# MCU.net
KiCad netlist of a schematic drawn in EAGLE
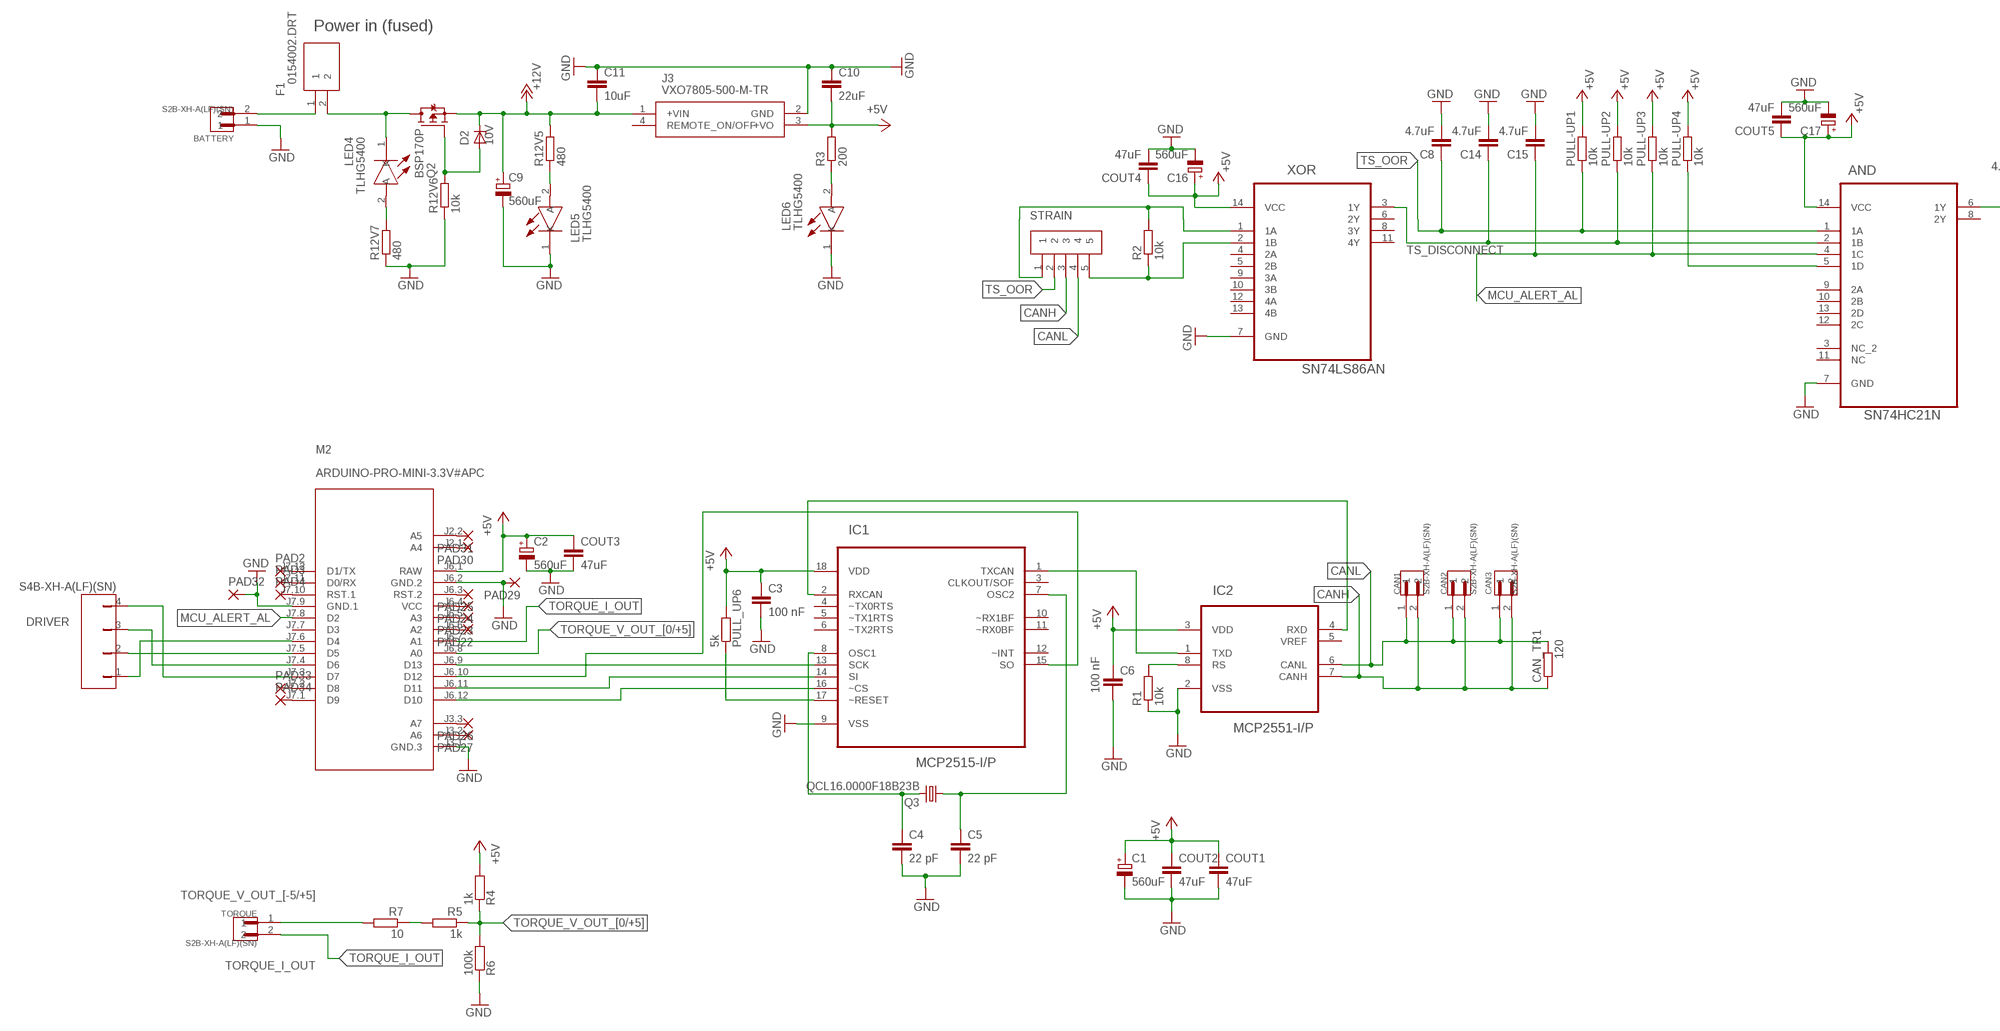
[diagram p0: schematic, sheet 1, part 1 of 2]
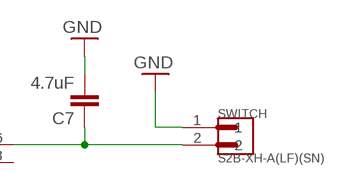
[diagram p1: schematic, sheet 1, part 2 of 2]

(export (version "E")
  (design (tool "Eeschema 10.0.6"))
  (components
    (comp (ref "AND")
      (value "SN74HC21N")
      (footprint "eagle-import:DIP254P762X508-14")
      (fields (field (name "MF") "Texas Instruments"))
      (libsource (lib "eagle-import") (part "SN74HC21N"))
    )
    (comp (ref "BATTERY")
      (value "S2B-XH-A(LF)(SN)")
      (footprint "eagle-import:JST_S2B-XH-A(LF)(SN)")
      (fields
        (field (name "DIGI-KEY_PART_NUMBER") "455-2257-ND")
        (field (name "MF") "JST Sales")
        (field (name "MP") "S2B-XH-A_LF__SN_")
      )
      (libsource (lib "eagle-import") (part "S2B-XH-A(LF)(SN)"))
    )
    (comp (ref "C1")
      (value "560uF")
      (footprint "eagle-import:PANASONIC_F")
      (libsource (lib "eagle-import") (part "CPOL-EUF"))
    )
    (comp (ref "C2")
      (value "560uF")
      (footprint "eagle-import:PANASONIC_F")
      (libsource (lib "eagle-import") (part "CPOL-EUF"))
    )
    (comp (ref "C3")
      (value "100 nF")
      (footprint "eagle-import:C0805")
      (libsource (lib "eagle-import") (part "C-EUC0805"))
    )
    (comp (ref "C4")
      (value "22 pF")
      (footprint "eagle-import:C0805")
      (libsource (lib "eagle-import") (part "C-EUC0805"))
    )
    (comp (ref "C5")
      (value "22 pF")
      (footprint "eagle-import:C0805")
      (libsource (lib "eagle-import") (part "C-EUC0805"))
    )
    (comp (ref "C6")
      (value "100 nF")
      (footprint "eagle-import:C0805")
      (libsource (lib "eagle-import") (part "C-EUC0805"))
    )
    (comp (ref "C7")
      (value "4.7uF")
      (footprint "eagle-import:C0805")
      (libsource (lib "eagle-import") (part "C-EUC0805"))
    )
    (comp (ref "C8")
      (value "4.7uF")
      (footprint "eagle-import:C0805")
      (libsource (lib "eagle-import") (part "C-EUC0805"))
    )
    (comp (ref "C9")
      (value "560uF")
      (footprint "eagle-import:PANASONIC_F")
      (libsource (lib "eagle-import") (part "CPOL-EUF"))
    )
    (comp (ref "C10")
      (value "22uF")
      (footprint "eagle-import:C0805")
      (libsource (lib "eagle-import") (part "C-EUC0805"))
    )
    (comp (ref "C11")
      (value "10uF")
      (footprint "eagle-import:C0805")
      (libsource (lib "eagle-import") (part "C-EUC0805"))
    )
    (comp (ref "C14")
      (value "4.7uF")
      (footprint "eagle-import:C0805")
      (libsource (lib "eagle-import") (part "C-EUC0805"))
    )
    (comp (ref "C15")
      (value "4.7uF")
      (footprint "eagle-import:C0805")
      (libsource (lib "eagle-import") (part "C-EUC0805"))
    )
    (comp (ref "C16")
      (value "560uF")
      (footprint "eagle-import:PANASONIC_F")
      (libsource (lib "eagle-import") (part "CPOL-EUF"))
    )
    (comp (ref "C17")
      (value "560uF")
      (footprint "eagle-import:PANASONIC_F")
      (libsource (lib "eagle-import") (part "CPOL-EUF"))
    )
    (comp (ref "CAN1")
      (value "S2B-XH-A(LF)(SN)")
      (footprint "eagle-import:JST_S2B-XH-A(LF)(SN)")
      (fields
        (field (name "DIGI-KEY_PART_NUMBER") "455-2257-ND")
        (field (name "MF") "JST Sales")
        (field (name "MP") "S2B-XH-A_LF__SN_")
      )
      (libsource (lib "eagle-import") (part "S2B-XH-A(LF)(SN)"))
    )
    (comp (ref "CAN2")
      (value "S2B-XH-A(LF)(SN)")
      (footprint "eagle-import:JST_S2B-XH-A(LF)(SN)")
      (fields
        (field (name "DIGI-KEY_PART_NUMBER") "455-2257-ND")
        (field (name "MF") "JST Sales")
        (field (name "MP") "S2B-XH-A_LF__SN_")
      )
      (libsource (lib "eagle-import") (part "S2B-XH-A(LF)(SN)"))
    )
    (comp (ref "CAN3")
      (value "S2B-XH-A(LF)(SN)")
      (footprint "eagle-import:JST_S2B-XH-A(LF)(SN)")
      (fields
        (field (name "DIGI-KEY_PART_NUMBER") "455-2257-ND")
        (field (name "MF") "JST Sales")
        (field (name "MP") "S2B-XH-A_LF__SN_")
      )
      (libsource (lib "eagle-import") (part "S2B-XH-A(LF)(SN)"))
    )
    (comp (ref "CAN_TR1")
      (value "120")
      (footprint "eagle-import:R0805")
      (libsource (lib "eagle-import") (part "R-EU_R0805"))
    )
    (comp (ref "COUT1")
      (value "47uF")
      (footprint "eagle-import:C0805")
      (libsource (lib "eagle-import") (part "C-EUC0805"))
    )
    (comp (ref "COUT2")
      (value "47uF")
      (footprint "eagle-import:C0805")
      (libsource (lib "eagle-import") (part "C-EUC0805"))
    )
    (comp (ref "COUT3")
      (value "47uF")
      (footprint "eagle-import:C0805")
      (libsource (lib "eagle-import") (part "C-EUC0805"))
    )
    (comp (ref "COUT4")
      (value "47uF")
      (footprint "eagle-import:C0805")
      (libsource (lib "eagle-import") (part "C-EUC0805"))
    )
    (comp (ref "COUT5")
      (value "47uF")
      (footprint "eagle-import:C0805")
      (libsource (lib "eagle-import") (part "C-EUC0805"))
    )
    (comp (ref "D2")
      (value "10V")
      (footprint "eagle-import:SMB")
      (libsource (lib "eagle-import") (part "ZENER-DIODESMB"))
    )
    (comp (ref "DRIVER")
      (value "S4B-XH-A(LF)(SN)")
      (footprint "eagle-import:S4B-XH-A(LF)(SN)")
      (fields (field (name "MF") "JST Sales") (field (name "MP") "S4B-XH-A_LF__SN_"))
      (libsource (lib "eagle-import") (part "S4B-XH-A(LF)(SN)"))
    )
    (comp (ref "F1")
      (value "0154002.DRT")
      (footprint "eagle-import:FUSM9750X381N")
      (fields (field (name "MOUSER_PART_NUMBER") "576-0154002.DRT"))
      (libsource (lib "eagle-import") (part "0154002.DRT"))
    )
    (comp (ref "IC1")
      (value "MCP2515-I/P")
      (footprint "eagle-import:DIP254P762X432-18")
      (fields (field (name "MF") "Microchip"))
      (libsource (lib "eagle-import") (part "MCP2515-I/P"))
    )
    (comp (ref "IC2")
      (value "MCP2551-I/P")
      (footprint "eagle-import:DIP254P762X432-8")
      (fields (field (name "MF") "Microchip"))
      (libsource (lib "eagle-import") (part "MCP2551-I/P"))
    )
    (comp (ref "J3")
      (value "VXO7805-500-M-TR")
      (footprint "eagle-import:VXO7805500MTR")
      (fields (field (name "MOUSER_PART_NUMBER") "490-VXO7805-500-M-TR"))
      (libsource (lib "eagle-import") (part "VXO7805-500-M-TR"))
    )
    (comp (ref "LED4")
      (value "TLHG5400")
      (footprint "eagle-import:TLHG5400")
      (fields (field (name "MOUSER_PART_NUMBER") "78-TLHG5400"))
      (libsource (lib "eagle-import") (part "TLHG5400"))
    )
    (comp (ref "LED5")
      (value "TLHG5400")
      (footprint "eagle-import:TLHG5400")
      (fields (field (name "MOUSER_PART_NUMBER") "78-TLHG5400"))
      (libsource (lib "eagle-import") (part "TLHG5400"))
    )
    (comp (ref "LED6")
      (value "TLHG5400")
      (footprint "eagle-import:TLHG5400")
      (fields (field (name "MOUSER_PART_NUMBER") "78-TLHG5400"))
      (libsource (lib "eagle-import") (part "TLHG5400"))
    )
    (comp (ref "M2")
      (value "ARDUINO-PRO-MINI-3.3V#APC")
      (footprint "eagle-import:ARDUINO-PRO-MINI#APC")
      (libsource (lib "eagle-import") (part "ARDUINO-PRO-MINI-#APC3.3V"))
    )
    (comp (ref "PAD2")
      (value "SMD2")
      (footprint "eagle-import:SMD1,27-2,54")
      (libsource (lib "eagle-import") (part "SMD2"))
    )
    (comp (ref "PAD3")
      (value "SMD2")
      (footprint "eagle-import:SMD1,27-2,54")
      (libsource (lib "eagle-import") (part "SMD2"))
    )
    (comp (ref "PAD4")
      (value "SMD2")
      (footprint "eagle-import:SMD1,27-2,54")
      (libsource (lib "eagle-import") (part "SMD2"))
    )
    (comp (ref "PAD22")
      (value "SMD2")
      (footprint "eagle-import:SMD1,27-2,54")
      (libsource (lib "eagle-import") (part "SMD2"))
    )
    (comp (ref "PAD23")
      (value "SMD2")
      (footprint "eagle-import:SMD1,27-2,54")
      (libsource (lib "eagle-import") (part "SMD2"))
    )
    (comp (ref "PAD24")
      (value "SMD2")
      (footprint "eagle-import:SMD1,27-2,54")
      (libsource (lib "eagle-import") (part "SMD2"))
    )
    (comp (ref "PAD25")
      (value "SMD2")
      (footprint "eagle-import:SMD1,27-2,54")
      (libsource (lib "eagle-import") (part "SMD2"))
    )
    (comp (ref "PAD26")
      (value "SMD2")
      (footprint "eagle-import:SMD1,27-2,54")
      (libsource (lib "eagle-import") (part "SMD2"))
    )
    (comp (ref "PAD27")
      (value "SMD2")
      (footprint "eagle-import:SMD1,27-2,54")
      (libsource (lib "eagle-import") (part "SMD2"))
    )
    (comp (ref "PAD29")
      (value "SMD2")
      (footprint "eagle-import:SMD1,27-2,54")
      (libsource (lib "eagle-import") (part "SMD2"))
    )
    (comp (ref "PAD30")
      (value "SMD2")
      (footprint "eagle-import:SMD1,27-2,54")
      (libsource (lib "eagle-import") (part "SMD2"))
    )
    (comp (ref "PAD31")
      (value "SMD2")
      (footprint "eagle-import:SMD1,27-2,54")
      (libsource (lib "eagle-import") (part "SMD2"))
    )
    (comp (ref "PAD32")
      (value "SMD2")
      (footprint "eagle-import:SMD1,27-2,54")
      (libsource (lib "eagle-import") (part "SMD2"))
    )
    (comp (ref "PAD33")
      (value "SMD2")
      (footprint "eagle-import:SMD1,27-2,54")
      (libsource (lib "eagle-import") (part "SMD2"))
    )
    (comp (ref "PAD34")
      (value "SMD2")
      (footprint "eagle-import:SMD1,27-2,54")
      (libsource (lib "eagle-import") (part "SMD2"))
    )
    (comp (ref "PULL-UP1")
      (value "10k")
      (footprint "eagle-import:R0805")
      (libsource (lib "eagle-import") (part "R-EU_R0805"))
    )
    (comp (ref "PULL-UP2")
      (value "10k")
      (footprint "eagle-import:R0805")
      (libsource (lib "eagle-import") (part "R-EU_R0805"))
    )
    (comp (ref "PULL-UP3")
      (value "10k")
      (footprint "eagle-import:R0805")
      (libsource (lib "eagle-import") (part "R-EU_R0805"))
    )
    (comp (ref "PULL-UP4")
      (value "10k")
      (footprint "eagle-import:R0805")
      (libsource (lib "eagle-import") (part "R-EU_R0805"))
    )
    (comp (ref "PULL_UP6")
      (value "5k")
      (footprint "eagle-import:R0805")
      (libsource (lib "eagle-import") (part "R-EU_R0805"))
    )
    (comp (ref "Q2")
      (value "BSP170P")
      (footprint "eagle-import:SOT223")
      (libsource (lib "eagle-import") (part "BSP170P"))
    )
    (comp (ref "Q3")
      (value "QCL16.0000F18B23B")
      (footprint "eagle-import:HC49_S")
      (libsource (lib "eagle-import") (part "CRYSTALHC49S"))
    )
    (comp (ref "R1")
      (value "10k")
      (footprint "eagle-import:R0805")
      (libsource (lib "eagle-import") (part "R-EU_R0805"))
    )
    (comp (ref "R2")
      (value "10k")
      (footprint "eagle-import:R0805")
      (libsource (lib "eagle-import") (part "R-EU_R0805"))
    )
    (comp (ref "R3")
      (value "200")
      (footprint "eagle-import:R0805")
      (libsource (lib "eagle-import") (part "R-EU_R0805"))
    )
    (comp (ref "R4")
      (value "1k")
      (footprint "eagle-import:R0805")
      (libsource (lib "eagle-import") (part "R-EU_R0805"))
    )
    (comp (ref "R5")
      (value "1k")
      (footprint "eagle-import:R0805")
      (libsource (lib "eagle-import") (part "R-EU_R0805"))
    )
    (comp (ref "R6")
      (value "100k")
      (footprint "eagle-import:R0805")
      (libsource (lib "eagle-import") (part "R-EU_R0805"))
    )
    (comp (ref "R7")
      (value "10")
      (footprint "eagle-import:R0805")
      (libsource (lib "eagle-import") (part "R-EU_R0805"))
    )
    (comp (ref "R12V5")
      (value "480")
      (footprint "eagle-import:R0805")
      (libsource (lib "eagle-import") (part "R-EU_R0805"))
    )
    (comp (ref "R12V6")
      (value "10k")
      (footprint "eagle-import:R0805")
      (libsource (lib "eagle-import") (part "R-EU_R0805"))
    )
    (comp (ref "R12V7")
      (value "480")
      (footprint "eagle-import:R0805")
      (libsource (lib "eagle-import") (part "R-EU_R0805"))
    )
    (comp (ref "STRAIN")
      (value "S5B-XH-A(LF)(SN)")
      (footprint "eagle-import:JST_S5B-XH-A(LF)(SN)")
      (fields (field (name "MF") "JST Sales") (field (name "MP") "S5B-XH-A_LF__SN_"))
      (libsource (lib "eagle-import") (part "S5B-XH-A(LF)(SN)"))
    )
    (comp (ref "SWITCH")
      (value "S2B-XH-A(LF)(SN)")
      (footprint "eagle-import:JST_S2B-XH-A(LF)(SN)")
      (fields
        (field (name "DIGI-KEY_PART_NUMBER") "455-2257-ND")
        (field (name "MF") "JST Sales")
        (field (name "MP") "S2B-XH-A_LF__SN_")
      )
      (libsource (lib "eagle-import") (part "S2B-XH-A(LF)(SN)"))
    )
    (comp (ref "TORQUE")
      (value "S2B-XH-A(LF)(SN)")
      (footprint "eagle-import:JST_S2B-XH-A(LF)(SN)")
      (fields
        (field (name "DIGI-KEY_PART_NUMBER") "455-2257-ND")
        (field (name "MF") "JST Sales")
        (field (name "MP") "S2B-XH-A_LF__SN_")
      )
      (libsource (lib "eagle-import") (part "S2B-XH-A(LF)(SN)"))
    )
    (comp (ref "XOR")
      (value "SN74LS86AN")
      (footprint "eagle-import:DIP254P762X508-14")
      (fields (field (name "MF") "Texas Instruments"))
      (libsource (lib "eagle-import") (part "SN74LS86AN"))
    )
  )
  (nets
    (net (code "1") (name "+5V") (class "Default")
      (node (ref "AND") (pin "14") (pinfunction "VCC_14") (pintype "power_in"))
      (node (ref "C1") (pin "+") (pinfunction "+_+") (pintype "passive"))
      (node (ref "C10") (pin "2") (pinfunction "2_2") (pintype "passive"))
      (node (ref "C16") (pin "+") (pinfunction "+_+") (pintype "passive"))
      (node (ref "C17") (pin "+") (pinfunction "+_+") (pintype "passive"))
      (node (ref "C2") (pin "+") (pinfunction "+_+") (pintype "passive"))
      (node (ref "C3") (pin "1") (pinfunction "1_1") (pintype "passive"))
      (node (ref "C6") (pin "1") (pinfunction "1_1") (pintype "passive"))
      (node (ref "COUT1") (pin "1") (pinfunction "1_1") (pintype "passive"))
      (node (ref "COUT2") (pin "1") (pinfunction "1_1") (pintype "passive"))
      (node (ref "COUT3") (pin "1") (pinfunction "1_1") (pintype "passive"))
      (node (ref "COUT4") (pin "1") (pinfunction "1_1") (pintype "passive"))
      (node (ref "COUT5") (pin "1") (pinfunction "1_1") (pintype "passive"))
      (node (ref "IC1") (pin "18") (pinfunction "VDD_18") (pintype "power_in"))
      (node (ref "IC2") (pin "3") (pinfunction "VDD_3") (pintype "power_in"))
      (node (ref "J3") (pin "3") (pinfunction "+VO_3") (pintype "bidirectional"))
      (node (ref "M2") (pin "J6.1") (pinfunction "RAW_J6.1") (pintype "power_in"))
      (node (ref "PULL-UP1") (pin "2") (pinfunction "2_2") (pintype "passive"))
      (node (ref "PULL-UP2") (pin "2") (pinfunction "2_2") (pintype "passive"))
      (node (ref "PULL-UP3") (pin "2") (pinfunction "2_2") (pintype "passive"))
      (node (ref "PULL-UP4") (pin "2") (pinfunction "2_2") (pintype "passive"))
      (node (ref "PULL_UP6") (pin "2") (pinfunction "2_2") (pintype "passive"))
      (node (ref "R3") (pin "2") (pinfunction "2_2") (pintype "passive"))
      (node (ref "R4") (pin "2") (pinfunction "2_2") (pintype "passive"))
      (node (ref "XOR") (pin "14") (pinfunction "VCC_14") (pintype "power_in"))
    )
    (net (code "2") (name "+12V") (class "Default")
      (node (ref "C11") (pin "2") (pinfunction "2_2") (pintype "passive"))
      (node (ref "C9") (pin "+") (pinfunction "+_+") (pintype "passive"))
      (node (ref "D2") (pin "C") (pinfunction "C_C") (pintype "passive"))
      (node (ref "J3") (pin "1") (pinfunction "+VIN_1") (pintype "bidirectional"))
      (node (ref "Q2") (pin "3") (pinfunction "S_3") (pintype "passive"))
      (node (ref "R12V5") (pin "2") (pinfunction "2_2") (pintype "passive"))
    )
    (net (code "3") (name "/TORQUE_V_OUT_[-5{slash}+5]") (class "Default")
      (node (ref "R7") (pin "2") (pinfunction "2_2") (pintype "passive"))
      (node (ref "TORQUE") (pin "1") (pinfunction "1_1") (pintype "passive"))
    )
    (net (code "4") (name "/TS_DISCONNECT") (class "Default")
      (node (ref "AND") (pin "2") (pinfunction "1B_2") (pintype "input"))
      (node (ref "C14") (pin "1") (pinfunction "1_1") (pintype "passive"))
      (node (ref "PULL-UP2") (pin "1") (pinfunction "1_1") (pintype "passive"))
      (node (ref "XOR") (pin "3") (pinfunction "1Y_3") (pintype "output"))
    )
    (net (code "5") (name "CANH") (class "Default")
      (node (ref "CAN1") (pin "2") (pinfunction "2_2") (pintype "passive"))
      (node (ref "CAN2") (pin "2") (pinfunction "2_2") (pintype "passive"))
      (node (ref "CAN3") (pin "2") (pinfunction "2_2") (pintype "passive"))
      (node (ref "CAN_TR1") (pin "1") (pinfunction "1_1") (pintype "passive"))
      (node (ref "IC2") (pin "7") (pinfunction "CANH_7") (pintype "bidirectional"))
      (node (ref "STRAIN") (pin "3") (pinfunction "3_3") (pintype "passive"))
    )
    (net (code "6") (name "CANL") (class "Default")
      (node (ref "CAN1") (pin "1") (pinfunction "1_1") (pintype "passive"))
      (node (ref "CAN2") (pin "1") (pinfunction "1_1") (pintype "passive"))
      (node (ref "CAN3") (pin "1") (pinfunction "1_1") (pintype "passive"))
      (node (ref "CAN_TR1") (pin "2") (pinfunction "2_2") (pintype "passive"))
      (node (ref "IC2") (pin "6") (pinfunction "CANL_6") (pintype "bidirectional"))
      (node (ref "STRAIN") (pin "4") (pinfunction "4_4") (pintype "passive"))
    )
    (net (code "7") (name "GND") (class "Default")
      (node (ref "AND") (pin "7") (pinfunction "GND_7") (pintype "passive"))
      (node (ref "BATTERY") (pin "1") (pinfunction "1_1") (pintype "passive"))
      (node (ref "C1") (pin "-") (pinfunction "-_-") (pintype "passive"))
      (node (ref "C10") (pin "1") (pinfunction "1_1") (pintype "passive"))
      (node (ref "C11") (pin "1") (pinfunction "1_1") (pintype "passive"))
      (node (ref "C14") (pin "2") (pinfunction "2_2") (pintype "passive"))
      (node (ref "C15") (pin "2") (pinfunction "2_2") (pintype "passive"))
      (node (ref "C16") (pin "-") (pinfunction "-_-") (pintype "passive"))
      (node (ref "C17") (pin "-") (pinfunction "-_-") (pintype "passive"))
      (node (ref "C2") (pin "-") (pinfunction "-_-") (pintype "passive"))
      (node (ref "C3") (pin "2") (pinfunction "2_2") (pintype "passive"))
      (node (ref "C4") (pin "2") (pinfunction "2_2") (pintype "passive"))
      (node (ref "C5") (pin "2") (pinfunction "2_2") (pintype "passive"))
      (node (ref "C6") (pin "2") (pinfunction "2_2") (pintype "passive"))
      (node (ref "C7") (pin "2") (pinfunction "2_2") (pintype "passive"))
      (node (ref "C8") (pin "2") (pinfunction "2_2") (pintype "passive"))
      (node (ref "C9") (pin "-") (pinfunction "-_-") (pintype "passive"))
      (node (ref "COUT1") (pin "2") (pinfunction "2_2") (pintype "passive"))
      (node (ref "COUT2") (pin "2") (pinfunction "2_2") (pintype "passive"))
      (node (ref "COUT3") (pin "2") (pinfunction "2_2") (pintype "passive"))
      (node (ref "COUT4") (pin "2") (pinfunction "2_2") (pintype "passive"))
      (node (ref "COUT5") (pin "2") (pinfunction "2_2") (pintype "passive"))
      (node (ref "IC1") (pin "9") (pinfunction "VSS_9") (pintype "power_in"))
      (node (ref "IC2") (pin "2") (pinfunction "VSS_2") (pintype "power_in"))
      (node (ref "J3") (pin "2") (pinfunction "GND_2") (pintype "bidirectional"))
      (node (ref "LED5") (pin "1") (pinfunction "K_1") (pintype "bidirectional"))
      (node (ref "LED6") (pin "1") (pinfunction "K_1") (pintype "bidirectional"))
      (node (ref "M2") (pin "J3.1") (pinfunction "GND.3_J3.1") (pintype "bidirectional"))
      (node (ref "M2") (pin "J6.2") (pinfunction "GND.2_J6.2") (pintype "power_in"))
      (node (ref "M2") (pin "J7.9") (pinfunction "GND.1_J7.9") (pintype "power_in"))
      (node (ref "PAD29") (pin "1") (pinfunction "P_1") (pintype "passive"))
      (node (ref "PAD32") (pin "1") (pinfunction "P_1") (pintype "passive"))
      (node (ref "R1") (pin "1") (pinfunction "1_1") (pintype "passive"))
      (node (ref "R12V6") (pin "1") (pinfunction "1_1") (pintype "passive"))
      (node (ref "R12V7") (pin "1") (pinfunction "1_1") (pintype "passive"))
      (node (ref "R6") (pin "1") (pinfunction "1_1") (pintype "passive"))
      (node (ref "SWITCH") (pin "1") (pinfunction "1_1") (pintype "passive"))
      (node (ref "XOR") (pin "7") (pinfunction "GND_7") (pintype "passive"))
    )
    (net (code "8") (name "MCU_ALERT_AL") (class "Default")
      (node (ref "AND") (pin "4") (pinfunction "1C_4") (pintype "input"))
      (node (ref "C15") (pin "1") (pinfunction "1_1") (pintype "passive"))
      (node (ref "M2") (pin "J7.8") (pinfunction "D2_J7.8") (pintype "bidirectional"))
      (node (ref "PULL-UP3") (pin "1") (pinfunction "1_1") (pintype "passive"))
    )
    (net (code "9") (name "Net-(AND-1D)") (class "Default")
      (node (ref "AND") (pin "5") (pinfunction "1D_5") (pintype "input"))
      (node (ref "PULL-UP4") (pin "1") (pinfunction "1_1") (pintype "passive"))
    )
    (net (code "10") (name "Net-(AND-1Y)") (class "Default")
      (node (ref "AND") (pin "6") (pinfunction "1Y_6") (pintype "output"))
      (node (ref "C7") (pin "1") (pinfunction "1_1") (pintype "passive"))
      (node (ref "SWITCH") (pin "2") (pinfunction "2_2") (pintype "passive"))
    )
    (net (code "11") (name "Net-(BATTERY-Pad2)") (class "Default")
      (node (ref "BATTERY") (pin "2") (pinfunction "2_2") (pintype "passive"))
      (node (ref "F1") (pin "1") (pinfunction "1_1") (pintype "bidirectional"))
    )
    (net (code "12") (name "Net-(IC1-OSC1)") (class "Default")
      (node (ref "C4") (pin "1") (pinfunction "1_1") (pintype "passive"))
      (node (ref "IC1") (pin "8") (pinfunction "OSC1_8") (pintype "input"))
      (node (ref "Q3") (pin "2") (pinfunction "2_2") (pintype "passive"))
    )
    (net (code "13") (name "Net-(IC1-OSC2)") (class "Default")
      (node (ref "C5") (pin "1") (pinfunction "1_1") (pintype "passive"))
      (node (ref "IC1") (pin "7") (pinfunction "OSC2_7") (pintype "output"))
      (node (ref "Q3") (pin "1") (pinfunction "1_1") (pintype "passive"))
    )
    (net (code "14") (name "Net-(IC1-RXCAN)") (class "Default")
      (node (ref "IC1") (pin "2") (pinfunction "RXCAN_2") (pintype "input"))
      (node (ref "IC2") (pin "4") (pinfunction "RXD_4") (pintype "output"))
    )
    (net (code "15") (name "Net-(IC1-SCK)") (class "Default")
      (node (ref "IC1") (pin "13") (pinfunction "SCK_13") (pintype "input"))
      (node (ref "M2") (pin "J6.9") (pinfunction "D13_J6.9") (pintype "bidirectional"))
    )
    (net (code "16") (name "Net-(IC1-SI)") (class "Default")
      (node (ref "IC1") (pin "14") (pinfunction "SI_14") (pintype "input"))
      (node (ref "M2") (pin "J6.11") (pinfunction "D11_J6.11") (pintype "bidirectional"))
    )
    (net (code "17") (name "Net-(IC1-SO)") (class "Default")
      (node (ref "IC1") (pin "15") (pinfunction "SO_15") (pintype "output"))
      (node (ref "M2") (pin "J6.10") (pinfunction "D12_J6.10") (pintype "bidirectional"))
    )
    (net (code "18") (name "Net-(IC1-TXCAN)") (class "Default")
      (node (ref "IC1") (pin "1") (pinfunction "TXCAN_1") (pintype "output"))
      (node (ref "IC2") (pin "1") (pinfunction "TXD_1") (pintype "input"))
    )
    (net (code "19") (name "Net-(IC1-~{CS})") (class "Default")
      (node (ref "IC1") (pin "16") (pinfunction "~{CS}_16") (pintype "input"))
      (node (ref "M2") (pin "J6.12") (pinfunction "D10_J6.12") (pintype "bidirectional"))
    )
    (net (code "20") (name "Net-(IC1-~{RESET})") (class "Default")
      (node (ref "IC1") (pin "17") (pinfunction "~{RESET}_17") (pintype "input"))
      (node (ref "PULL_UP6") (pin "1") (pinfunction "1_1") (pintype "passive"))
    )
    (net (code "21") (name "Net-(IC2-RS)") (class "Default")
      (node (ref "IC2") (pin "8") (pinfunction "RS_8") (pintype "input"))
      (node (ref "R1") (pin "2") (pinfunction "2_2") (pintype "passive"))
    )
    (net (code "22") (name "Net-(LED4-A)") (class "Default")
      (node (ref "LED4") (pin "2") (pinfunction "A_2") (pintype "bidirectional"))
      (node (ref "R12V7") (pin "2") (pinfunction "2_2") (pintype "passive"))
    )
    (net (code "23") (name "Net-(LED4-K)") (class "Default")
      (node (ref "F1") (pin "2") (pinfunction "2_2") (pintype "bidirectional"))
      (node (ref "LED4") (pin "1") (pinfunction "K_1") (pintype "bidirectional"))
      (node (ref "Q2") (pin "2") (pinfunction "D_2") (pintype "passive"))
      (node (ref "Q2") (pin "4") (pinfunction "D_4") (pintype "passive"))
    )
    (net (code "24") (name "Net-(LED5-A)") (class "Default")
      (node (ref "LED5") (pin "2") (pinfunction "A_2") (pintype "bidirectional"))
      (node (ref "R12V5") (pin "1") (pinfunction "1_1") (pintype "passive"))
    )
    (net (code "25") (name "Net-(LED6-A)") (class "Default")
      (node (ref "LED6") (pin "2") (pinfunction "A_2") (pintype "bidirectional"))
      (node (ref "R3") (pin "1") (pinfunction "1_1") (pintype "passive"))
    )
    (net (code "26") (name "Net-(M2-A2)") (class "Default")
      (node (ref "M2") (pin "J6.6") (pinfunction "A2_J6.6") (pintype "bidirectional"))
      (node (ref "PAD22") (pin "1") (pinfunction "P_1") (pintype "passive"))
    )
    (net (code "27") (name "Net-(M2-A3)") (class "Default")
      (node (ref "M2") (pin "J6.5") (pinfunction "A3_J6.5") (pintype "bidirectional"))
      (node (ref "PAD23") (pin "1") (pinfunction "P_1") (pintype "passive"))
    )
    (net (code "28") (name "Net-(M2-A4)") (class "Default")
      (node (ref "M2") (pin "J2.1") (pinfunction "A4_J2.1") (pintype "bidirectional"))
      (node (ref "PAD30") (pin "1") (pinfunction "P_1") (pintype "passive"))
    )
    (net (code "29") (name "Net-(M2-A5)") (class "Default")
      (node (ref "M2") (pin "J2.2") (pinfunction "A5_J2.2") (pintype "bidirectional"))
      (node (ref "PAD31") (pin "1") (pinfunction "P_1") (pintype "passive"))
    )
    (net (code "30") (name "Net-(M2-A6)") (class "Default")
      (node (ref "M2") (pin "J3.2") (pinfunction "A6_J3.2") (pintype "bidirectional"))
      (node (ref "PAD27") (pin "1") (pinfunction "P_1") (pintype "passive"))
    )
    (net (code "31") (name "Net-(M2-A7)") (class "Default")
      (node (ref "M2") (pin "J3.3") (pinfunction "A7_J3.3") (pintype "bidirectional"))
      (node (ref "PAD26") (pin "1") (pinfunction "P_1") (pintype "passive"))
    )
    (net (code "32") (name "Net-(M2-D0{slash}RX)") (class "Default")
      (node (ref "M2") (pin "J7.11") (pinfunction "D0/RX_J7.11") (pintype "bidirectional"))
      (node (ref "PAD3") (pin "1") (pinfunction "P_1") (pintype "passive"))
    )
    (net (code "33") (name "Net-(M2-D1{slash}TX)") (class "Default")
      (node (ref "M2") (pin "J7.12") (pinfunction "D1/TX_J7.12") (pintype "bidirectional"))
      (node (ref "PAD2") (pin "1") (pinfunction "P_1") (pintype "passive"))
    )
    (net (code "34") (name "Net-(M2-D4)") (class "Default")
      (node (ref "DRIVER") (pin "1") (pinfunction "1_1") (pintype "passive"))
      (node (ref "M2") (pin "J7.6") (pinfunction "D4_J7.6") (pintype "bidirectional"))
    )
    (net (code "35") (name "Net-(M2-D5)") (class "Default")
      (node (ref "DRIVER") (pin "2") (pinfunction "2_2") (pintype "passive"))
      (node (ref "M2") (pin "J7.5") (pinfunction "D5_J7.5") (pintype "bidirectional"))
    )
    (net (code "36") (name "Net-(M2-D6)") (class "Default")
      (node (ref "DRIVER") (pin "3") (pinfunction "3_3") (pintype "passive"))
      (node (ref "M2") (pin "J7.4") (pinfunction "D6_J7.4") (pintype "bidirectional"))
    )
    (net (code "37") (name "Net-(M2-D7)") (class "Default")
      (node (ref "DRIVER") (pin "4") (pinfunction "4_4") (pintype "passive"))
      (node (ref "M2") (pin "J7.3") (pinfunction "D7_J7.3") (pintype "bidirectional"))
    )
    (net (code "38") (name "Net-(M2-D8)") (class "Default")
      (node (ref "M2") (pin "J7.2") (pinfunction "D8_J7.2") (pintype "bidirectional"))
      (node (ref "PAD33") (pin "1") (pinfunction "P_1") (pintype "passive"))
    )
    (net (code "39") (name "Net-(M2-D9)") (class "Default")
      (node (ref "M2") (pin "J7.1") (pinfunction "D9_J7.1") (pintype "bidirectional"))
      (node (ref "PAD34") (pin "1") (pinfunction "P_1") (pintype "passive"))
    )
    (net (code "40") (name "Net-(M2-RST.1)") (class "Default")
      (node (ref "M2") (pin "J7.10") (pinfunction "RST.1_J7.10") (pintype "bidirectional"))
      (node (ref "PAD4") (pin "1") (pinfunction "P_1") (pintype "passive"))
    )
    (net (code "41") (name "Net-(M2-RST.2)") (class "Default")
      (node (ref "M2") (pin "J6.3") (pinfunction "RST.2_J6.3") (pintype "bidirectional"))
      (node (ref "PAD25") (pin "1") (pinfunction "P_1") (pintype "passive"))
    )
    (net (code "42") (name "Net-(M2-VCC)") (class "Default")
      (node (ref "M2") (pin "J6.4") (pinfunction "VCC_J6.4") (pintype "power_in"))
      (node (ref "PAD24") (pin "1") (pinfunction "P_1") (pintype "passive"))
    )
    (net (code "43") (name "Net-(Q2-G)") (class "Default")
      (node (ref "D2") (pin "A") (pinfunction "A_A") (pintype "passive"))
      (node (ref "Q2") (pin "1") (pinfunction "G_1") (pintype "passive"))
      (node (ref "R12V6") (pin "2") (pinfunction "2_2") (pintype "passive"))
    )
    (net (code "44") (name "Net-(R5-Pad2)") (class "Default")
      (node (ref "R5") (pin "2") (pinfunction "2_2") (pintype "passive"))
      (node (ref "R7") (pin "1") (pinfunction "1_1") (pintype "passive"))
    )
    (net (code "45") (name "Net-(XOR-1A)") (class "Default")
      (node (ref "R2") (pin "2") (pinfunction "2_2") (pintype "passive"))
      (node (ref "STRAIN") (pin "1") (pinfunction "1_1") (pintype "passive"))
      (node (ref "XOR") (pin "1") (pinfunction "1A_1") (pintype "input"))
    )
    (net (code "46") (name "Net-(XOR-1B)") (class "Default")
      (node (ref "R2") (pin "1") (pinfunction "1_1") (pintype "passive"))
      (node (ref "STRAIN") (pin "5") (pinfunction "5_5") (pintype "passive"))
      (node (ref "XOR") (pin "2") (pinfunction "1B_2") (pintype "input"))
    )
    (net (code "47") (name "TORQUE_I_OUT") (class "Default")
      (node (ref "M2") (pin "J6.7") (pinfunction "A1_J6.7") (pintype "bidirectional"))
      (node (ref "TORQUE") (pin "2") (pinfunction "2_2") (pintype "passive"))
    )
    (net (code "48") (name "TORQUE_V_OUT_[0{slash}+5]") (class "Default")
      (node (ref "M2") (pin "J6.8") (pinfunction "A0_J6.8") (pintype "bidirectional"))
      (node (ref "R4") (pin "1") (pinfunction "1_1") (pintype "passive"))
      (node (ref "R5") (pin "1") (pinfunction "1_1") (pintype "passive"))
      (node (ref "R6") (pin "2") (pinfunction "2_2") (pintype "passive"))
    )
    (net (code "49") (name "TS_OOR") (class "Default")
      (node (ref "AND") (pin "1") (pinfunction "1A_1") (pintype "input"))
      (node (ref "C8") (pin "1") (pinfunction "1_1") (pintype "passive"))
      (node (ref "PULL-UP1") (pin "1") (pinfunction "1_1") (pintype "passive"))
      (node (ref "STRAIN") (pin "2") (pinfunction "2_2") (pintype "passive"))
    )
    (net (code "50") (name "unconnected-(AND-2A-Pad9)") (class "Default")
      (node (ref "AND") (pin "9") (pinfunction "2A_9") (pintype "input"))
    )
    (net (code "51") (name "unconnected-(AND-2B-Pad10)") (class "Default")
      (node (ref "AND") (pin "10") (pinfunction "2B_10") (pintype "input"))
    )
    (net (code "52") (name "unconnected-(AND-2C-Pad12)") (class "Default")
      (node (ref "AND") (pin "12") (pinfunction "2C_12") (pintype "input"))
    )
    (net (code "53") (name "unconnected-(AND-2D-Pad13)") (class "Default")
      (node (ref "AND") (pin "13") (pinfunction "2D_13") (pintype "input"))
    )
    (net (code "54") (name "unconnected-(AND-2Y-Pad8)") (class "Default")
      (node (ref "AND") (pin "8") (pinfunction "2Y_8") (pintype "output"))
    )
    (net (code "55") (name "unconnected-(AND-NC-Pad11)") (class "Default")
      (node (ref "AND") (pin "11") (pinfunction "NC_11") (pintype "no_connect"))
    )
    (net (code "56") (name "unconnected-(AND-NC_2-Pad3)") (class "Default")
      (node (ref "AND") (pin "3") (pinfunction "NC_2_3") (pintype "no_connect"))
    )
    (net (code "57") (name "unconnected-(IC1-CLKOUT{slash}SOF-Pad3)") (class "Default")
      (node (ref "IC1") (pin "3") (pinfunction "CLKOUT/SOF_3") (pintype "output"))
    )
    (net (code "58") (name "unconnected-(IC1-~{INT}-Pad12)") (class "Default")
      (node (ref "IC1") (pin "12") (pinfunction "~{INT}_12") (pintype "output"))
    )
    (net (code "59") (name "unconnected-(IC1-~{RX0BF}-Pad11)") (class "Default")
      (node (ref "IC1") (pin "11") (pinfunction "~{RX0BF}_11") (pintype "output"))
    )
    (net (code "60") (name "unconnected-(IC1-~{RX1BF}-Pad10)") (class "Default")
      (node (ref "IC1") (pin "10") (pinfunction "~{RX1BF}_10") (pintype "output"))
    )
    (net (code "61") (name "unconnected-(IC1-~{TX0RTS}-Pad4)") (class "Default")
      (node (ref "IC1") (pin "4") (pinfunction "~{TX0RTS}_4") (pintype "input"))
    )
    (net (code "62") (name "unconnected-(IC1-~{TX1RTS}-Pad5)") (class "Default")
      (node (ref "IC1") (pin "5") (pinfunction "~{TX1RTS}_5") (pintype "input"))
    )
    (net (code "63") (name "unconnected-(IC1-~{TX2RTS}-Pad6)") (class "Default")
      (node (ref "IC1") (pin "6") (pinfunction "~{TX2RTS}_6") (pintype "input"))
    )
    (net (code "64") (name "unconnected-(IC2-VREF-Pad5)") (class "Default")
      (node (ref "IC2") (pin "5") (pinfunction "VREF_5") (pintype "output"))
    )
    (net (code "65") (name "unconnected-(J3-REMOTE_ON{slash}OFF-Pad4)") (class "Default")
      (node (ref "J3") (pin "4") (pinfunction "REMOTE_ON/OFF_4") (pintype "bidirectional"))
    )
    (net (code "66") (name "unconnected-(M2-D3-PadJ7.7)") (class "Default")
      (node (ref "M2") (pin "J7.7") (pinfunction "D3_J7.7") (pintype "bidirectional"))
    )
    (net (code "67") (name "unconnected-(XOR-2A-Pad4)") (class "Default")
      (node (ref "XOR") (pin "4") (pinfunction "2A_4") (pintype "input"))
    )
    (net (code "68") (name "unconnected-(XOR-2B-Pad5)") (class "Default")
      (node (ref "XOR") (pin "5") (pinfunction "2B_5") (pintype "input"))
    )
    (net (code "69") (name "unconnected-(XOR-2Y-Pad6)") (class "Default")
      (node (ref "XOR") (pin "6") (pinfunction "2Y_6") (pintype "output"))
    )
    (net (code "70") (name "unconnected-(XOR-3A-Pad9)") (class "Default")
      (node (ref "XOR") (pin "9") (pinfunction "3A_9") (pintype "input"))
    )
    (net (code "71") (name "unconnected-(XOR-3B-Pad10)") (class "Default")
      (node (ref "XOR") (pin "10") (pinfunction "3B_10") (pintype "input"))
    )
    (net (code "72") (name "unconnected-(XOR-3Y-Pad8)") (class "Default")
      (node (ref "XOR") (pin "8") (pinfunction "3Y_8") (pintype "output"))
    )
    (net (code "73") (name "unconnected-(XOR-4A-Pad12)") (class "Default")
      (node (ref "XOR") (pin "12") (pinfunction "4A_12") (pintype "input"))
    )
    (net (code "74") (name "unconnected-(XOR-4B-Pad13)") (class "Default")
      (node (ref "XOR") (pin "13") (pinfunction "4B_13") (pintype "input"))
    )
    (net (code "75") (name "unconnected-(XOR-4Y-Pad11)") (class "Default")
      (node (ref "XOR") (pin "11") (pinfunction "4Y_11") (pintype "output"))
    )
  )
)
